# Encoders.net
KiCad netlist of a schematic drawn in Altium Designer
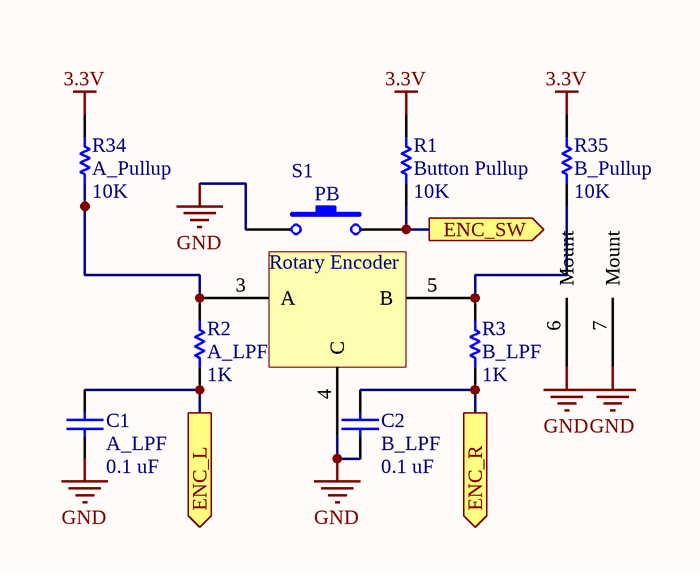
[diagram p0: Encoders.SchDoc]

(export (version "E")
  (design (tool "Eeschema 10.0.6"))
  (components
    (comp (ref "C1")
      (value "A_LPF")
      (footprint "C0805")
      (description "Capacitor")
      (fields (field (name "ALTIUM_VALUE") "0.1 uF") (field (name "PUBLISHER") "Altium Limited"))
      (libsource (lib "Miscellaneous Devices") (part "Cap"))
    )
    (comp (ref "C2")
      (value "B_LPF")
      (footprint "C0805")
      (description "Capacitor")
      (fields (field (name "ALTIUM_VALUE") "0.1 uF") (field (name "PUBLISHER") "Altium Limited"))
      (libsource (lib "Miscellaneous Devices") (part "Cap"))
    )
    (comp (ref "R1")
      (value "Button Pullup")
      (footprint "6-0805_N")
      (description "Resistor")
      (fields (field (name "ALTIUM_VALUE") "10K") (field (name "PUBLISHER") "Altium Limited"))
      (libsource (lib "Miscellaneous Devices") (part "Res1"))
    )
    (comp (ref "R2")
      (value "A_LPF")
      (footprint "6-0805_N")
      (description "Resistor")
      (fields (field (name "ALTIUM_VALUE") "1K") (field (name "PUBLISHER") "Altium Limited"))
      (libsource (lib "Miscellaneous Devices") (part "Res1"))
    )
    (comp (ref "R3")
      (value "B_LPF")
      (footprint "6-0805_N")
      (description "Resistor")
      (fields (field (name "ALTIUM_VALUE") "1K") (field (name "PUBLISHER") "Altium Limited"))
      (libsource (lib "Miscellaneous Devices") (part "Res1"))
    )
    (comp (ref "R34")
      (value "A_Pullup")
      (footprint "6-0805_N")
      (description "Resistor")
      (fields (field (name "ALTIUM_VALUE") "10K") (field (name "PUBLISHER") "Altium Limited"))
      (libsource (lib "Miscellaneous Devices") (part "Res1"))
    )
    (comp (ref "R35")
      (value "B_Pullup")
      (footprint "6-0805_N")
      (description "Resistor")
      (fields (field (name "ALTIUM_VALUE") "10K") (field (name "PUBLISHER") "Altium Limited"))
      (libsource (lib "Miscellaneous Devices") (part "Res1"))
    )
    (comp (ref "S1")
      (value "Rotary Encoder")
      (footprint "Rotary Encoder SF")
      (libsource (lib "FlexControl") (part "Rotary Encoder"))
    )
  )
  (nets
    (net (code "1") (name "/ENC_L") (class "Default")
      (node (ref "C1") (pin "2") (pinfunction "2_2") (pintype "passive"))
      (node (ref "R2") (pin "2") (pinfunction "2_2") (pintype "passive"))
    )
    (net (code "2") (name "/ENC_R") (class "Default")
      (node (ref "C2") (pin "2") (pinfunction "2_2") (pintype "passive"))
      (node (ref "R3") (pin "2") (pinfunction "2_2") (pintype "passive"))
    )
    (net (code "3") (name "/ENC_SW") (class "Default")
      (node (ref "R1") (pin "2") (pinfunction "2_2") (pintype "passive"))
      (node (ref "S1") (pin "2") (pinfunction "2_2") (pintype "passive"))
    )
    (net (code "4") (name "3.3V") (class "Default")
      (node (ref "R1") (pin "1") (pinfunction "1_1") (pintype "passive"))
      (node (ref "R34") (pin "1") (pinfunction "1_1") (pintype "passive"))
      (node (ref "R35") (pin "1") (pinfunction "1_1") (pintype "passive"))
    )
    (net (code "5") (name "GND") (class "Default")
      (node (ref "C1") (pin "1") (pinfunction "1_1") (pintype "passive"))
      (node (ref "C2") (pin "1") (pinfunction "1_1") (pintype "passive"))
      (node (ref "S1") (pin "1") (pinfunction "1_1") (pintype "passive"))
      (node (ref "S1") (pin "4") (pinfunction "C_4") (pintype "passive"))
      (node (ref "S1") (pin "6") (pinfunction "Mount_6") (pintype "passive"))
      (node (ref "S1") (pin "7") (pinfunction "Mount_7") (pintype "passive"))
    )
    (net (code "6") (name "Net-(S1-A)") (class "Default")
      (node (ref "R2") (pin "1") (pinfunction "1_1") (pintype "passive"))
      (node (ref "R34") (pin "2") (pinfunction "2_2") (pintype "passive"))
      (node (ref "S1") (pin "3") (pinfunction "A_3") (pintype "passive"))
    )
    (net (code "7") (name "Net-(S1-B)") (class "Default")
      (node (ref "R3") (pin "1") (pinfunction "1_1") (pintype "passive"))
      (node (ref "R35") (pin "2") (pinfunction "2_2") (pintype "passive"))
      (node (ref "S1") (pin "5") (pinfunction "B_5") (pintype "passive"))
    )
  )
)
